# LV.net
KiCad netlist of a schematic drawn in EAGLE
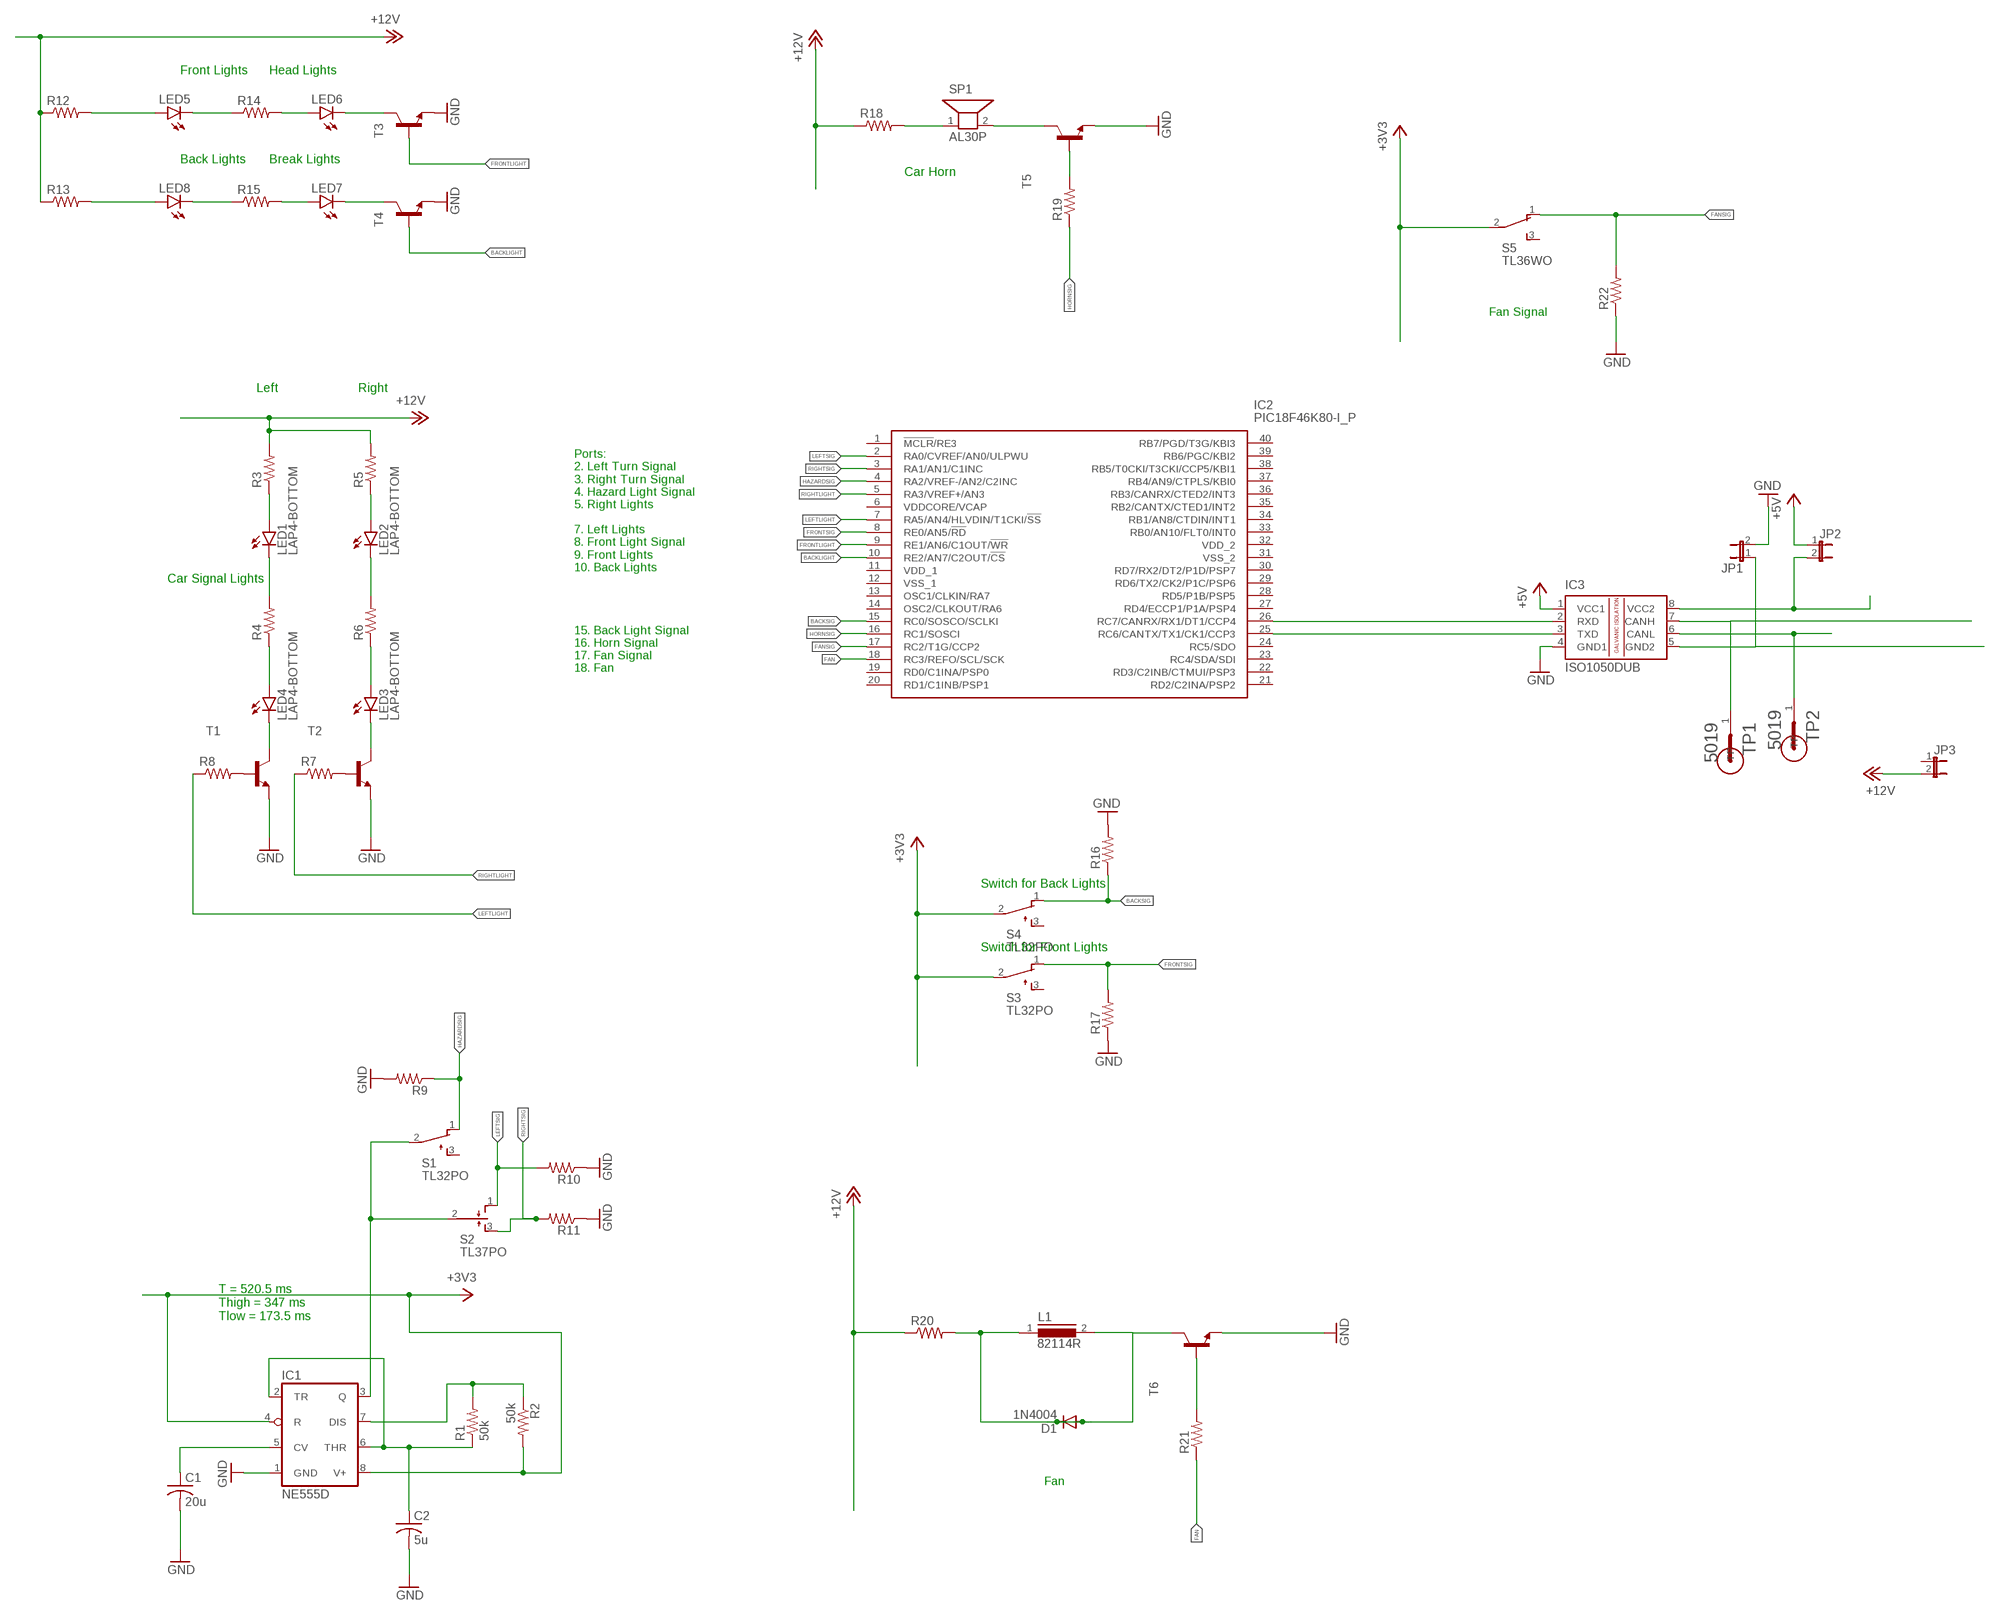
[diagram p0: schematic, sheet 1]

(export (version "E")
  (design (tool "Eeschema 10.0.6"))
  (components
    (comp (ref "C1")
      (value "20u")
      (footprint "eagle-import:C025-024X044")
      (libsource (lib "eagle-import") (part "C-US025-024X044"))
    )
    (comp (ref "C2")
      (value "5u")
      (footprint "eagle-import:C025-024X044")
      (libsource (lib "eagle-import") (part "C-US025-024X044"))
    )
    (comp (ref "D1")
      (value "1N4004")
      (footprint "eagle-import:DO41-10")
      (libsource (lib "eagle-import") (part "1N4004"))
    )
    (comp (ref "IC1")
      (value "NE555D")
      (footprint "eagle-import:SO08")
      (libsource (lib "eagle-import") (part "555DNE"))
    )
    (comp (ref "IC2")
      (value "PIC18F46K80-I_P")
      (footprint "eagle-import:DIP1778W58P254L5175H635Q40N")
      (fields
        (field (name "MANUFACTURER_PART_NUMBER") "PIC18F46K80-I/P")
        (field (name "RS_PART_NUMBER") "7154687P")
      )
      (libsource (lib "eagle-import") (part "PIC18F46K80-I_P"))
    )
    (comp (ref "IC3")
      (value "ISO1050DUB")
      (footprint "eagle-import:DUB-R-PDSO-G8")
      (fields (field (name "MPN") "ISO1050DUBR"))
      (libsource (lib "eagle-import") (part "ISO1050DUB"))
    )
    (comp (ref "JP1")
      (value "JP1E")
      (footprint "eagle-import:JP1")
      (libsource (lib "eagle-import") (part "JP1E"))
    )
    (comp (ref "JP2")
      (value "JP1E")
      (footprint "eagle-import:JP1")
      (libsource (lib "eagle-import") (part "JP1E"))
    )
    (comp (ref "JP3")
      (value "JP1E")
      (footprint "eagle-import:JP1")
      (libsource (lib "eagle-import") (part "JP1E"))
    )
    (comp (ref "L1")
      (value "82114R")
      (footprint "eagle-import:82114R")
      (libsource (lib "eagle-import") (part "82114R"))
    )
    (comp (ref "LED1")
      (value "LAP4-BOTTOM")
      (footprint "eagle-import:P47F-BOTTOM")
      (libsource (lib "eagle-import") (part "P4-BOTTOMLA"))
    )
    (comp (ref "LED2")
      (value "LAP4-BOTTOM")
      (footprint "eagle-import:P47F-BOTTOM")
      (libsource (lib "eagle-import") (part "P4-BOTTOMLA"))
    )
    (comp (ref "LED3")
      (value "LAP4-BOTTOM")
      (footprint "eagle-import:P47F-BOTTOM")
      (libsource (lib "eagle-import") (part "P4-BOTTOMLA"))
    )
    (comp (ref "LED4")
      (value "LAP4-BOTTOM")
      (footprint "eagle-import:P47F-BOTTOM")
      (libsource (lib "eagle-import") (part "P4-BOTTOMLA"))
    )
    (comp (ref "LED5")
      (value "LED")
      (footprint "eagle-import:SMARTLED-TTW")
      (libsource (lib "eagle-import") (part "LED"))
    )
    (comp (ref "LED6")
      (value "LED")
      (footprint "eagle-import:SMARTLED-TTW")
      (libsource (lib "eagle-import") (part "LED"))
    )
    (comp (ref "LED7")
      (value "LED")
      (footprint "eagle-import:SMARTLED-TTW")
      (libsource (lib "eagle-import") (part "LED"))
    )
    (comp (ref "LED8")
      (value "LED")
      (footprint "eagle-import:SMARTLED-TTW")
      (libsource (lib "eagle-import") (part "LED"))
    )
    (comp (ref "R1")
      (value "50k")
      (footprint "eagle-import:0204_7")
      (libsource (lib "eagle-import") (part "R-US_0204/7"))
    )
    (comp (ref "R2")
      (value "50k")
      (footprint "eagle-import:0204_7")
      (libsource (lib "eagle-import") (part "R-US_0204/7"))
    )
    (comp (ref "R3")
      (value "R-US_0204/7")
      (footprint "eagle-import:0204_7")
      (libsource (lib "eagle-import") (part "R-US_0204/7"))
    )
    (comp (ref "R4")
      (value "R-US_0204/7")
      (footprint "eagle-import:0204_7")
      (libsource (lib "eagle-import") (part "R-US_0204/7"))
    )
    (comp (ref "R5")
      (value "R-US_0204/7")
      (footprint "eagle-import:0204_7")
      (libsource (lib "eagle-import") (part "R-US_0204/7"))
    )
    (comp (ref "R6")
      (value "R-US_0204/7")
      (footprint "eagle-import:0204_7")
      (libsource (lib "eagle-import") (part "R-US_0204/7"))
    )
    (comp (ref "R7")
      (value "R-US_0204/7")
      (footprint "eagle-import:0204_7")
      (libsource (lib "eagle-import") (part "R-US_0204/7"))
    )
    (comp (ref "R8")
      (value "R-US_0204/7")
      (footprint "eagle-import:0204_7")
      (libsource (lib "eagle-import") (part "R-US_0204/7"))
    )
    (comp (ref "R9")
      (value "R-US_0204/7")
      (footprint "eagle-import:0204_7")
      (libsource (lib "eagle-import") (part "R-US_0204/7"))
    )
    (comp (ref "R10")
      (value "R-US_0204/7")
      (footprint "eagle-import:0204_7")
      (libsource (lib "eagle-import") (part "R-US_0204/7"))
    )
    (comp (ref "R11")
      (value "R-US_0204/7")
      (footprint "eagle-import:0204_7")
      (libsource (lib "eagle-import") (part "R-US_0204/7"))
    )
    (comp (ref "R12")
      (value "R-US_0204/7")
      (footprint "eagle-import:0204_7")
      (libsource (lib "eagle-import") (part "R-US_0204/7"))
    )
    (comp (ref "R13")
      (value "R-US_0204/7")
      (footprint "eagle-import:0204_7")
      (libsource (lib "eagle-import") (part "R-US_0204/7"))
    )
    (comp (ref "R14")
      (value "R-US_0204/7")
      (footprint "eagle-import:0204_7")
      (libsource (lib "eagle-import") (part "R-US_0204/7"))
    )
    (comp (ref "R15")
      (value "R-US_0204/7")
      (footprint "eagle-import:0204_7")
      (libsource (lib "eagle-import") (part "R-US_0204/7"))
    )
    (comp (ref "R16")
      (value "R-US_0204/7")
      (footprint "eagle-import:0204_7")
      (libsource (lib "eagle-import") (part "R-US_0204/7"))
    )
    (comp (ref "R17")
      (value "R-US_0204/7")
      (footprint "eagle-import:0204_7")
      (libsource (lib "eagle-import") (part "R-US_0204/7"))
    )
    (comp (ref "R18")
      (value "R-US_0204/7")
      (footprint "eagle-import:0204_7")
      (libsource (lib "eagle-import") (part "R-US_0204/7"))
    )
    (comp (ref "R19")
      (value "R-US_0204/7")
      (footprint "eagle-import:0204_7")
      (libsource (lib "eagle-import") (part "R-US_0204/7"))
    )
    (comp (ref "R20")
      (value "R-US_0204/7")
      (footprint "eagle-import:0204_7")
      (libsource (lib "eagle-import") (part "R-US_0204/7"))
    )
    (comp (ref "R21")
      (value "R-US_0204/7")
      (footprint "eagle-import:0204_7")
      (libsource (lib "eagle-import") (part "R-US_0204/7"))
    )
    (comp (ref "R22")
      (value "R-US_0204/7")
      (footprint "eagle-import:0204_7")
      (libsource (lib "eagle-import") (part "R-US_0204/7"))
    )
    (comp (ref "S1")
      (value "TL32PO")
      (footprint "eagle-import:TL3XPO")
      (libsource (lib "eagle-import") (part "TL32PO"))
    )
    (comp (ref "S2")
      (value "TL37PO")
      (footprint "eagle-import:TL3XPO")
      (libsource (lib "eagle-import") (part "TL37PO"))
    )
    (comp (ref "S3")
      (value "TL32PO")
      (footprint "eagle-import:TL3XPO")
      (libsource (lib "eagle-import") (part "TL32PO"))
    )
    (comp (ref "S4")
      (value "TL32PO")
      (footprint "eagle-import:TL3XPO")
      (libsource (lib "eagle-import") (part "TL32PO"))
    )
    (comp (ref "S5")
      (value "TL36WO")
      (footprint "eagle-import:TL3XWO")
      (libsource (lib "eagle-import") (part "TL36WO"))
    )
    (comp (ref "SP1")
      (value "AL30P")
      (footprint "eagle-import:AL30P")
      (libsource (lib "eagle-import") (part "AL30P"))
    )
    (comp (ref "T1")
      (value "-NPN-SOT23-EBC")
      (footprint "eagle-import:SOT23-EBC")
      (libsource (lib "eagle-import") (part "transistor_402_-NPN-SOT23-EBC"))
    )
    (comp (ref "T2")
      (value "-NPN-SOT23-EBC")
      (footprint "eagle-import:SOT23-EBC")
      (libsource (lib "eagle-import") (part "transistor_402_-NPN-SOT23-EBC"))
    )
    (comp (ref "T3")
      (value "-NPN-SOT23-EBC")
      (footprint "eagle-import:SOT23-EBC")
      (libsource (lib "eagle-import") (part "transistor_402_-NPN-SOT23-EBC"))
    )
    (comp (ref "T4")
      (value "-NPN-SOT23-EBC")
      (footprint "eagle-import:SOT23-EBC")
      (libsource (lib "eagle-import") (part "transistor_402_-NPN-SOT23-EBC"))
    )
    (comp (ref "T5")
      (value "-NPN-TO92")
      (footprint "eagle-import:TO92")
      (libsource (lib "eagle-import") (part "-NPN-TO92"))
    )
    (comp (ref "T6")
      (value "-NPN-TO92")
      (footprint "eagle-import:TO92")
      (libsource (lib "eagle-import") (part "-NPN-TO92"))
    )
    (comp (ref "TP1")
      (value "5019")
      (footprint "eagle-import:TP380X203")
      (fields (field (name "MF") "Keystone Electronics"))
      (libsource (lib "eagle-import") (part "5019"))
    )
    (comp (ref "TP2")
      (value "5019")
      (footprint "eagle-import:TP380X203")
      (fields (field (name "MF") "Keystone Electronics"))
      (libsource (lib "eagle-import") (part "5019"))
    )
  )
  (nets
    (net (code "1") (name "+3V3") (class "Default")
      (node (ref "IC1") (pin "4") (pinfunction "R_4") (pintype "input"))
      (node (ref "IC1") (pin "8") (pinfunction "V+_8") (pintype "power_in"))
      (node (ref "R2") (pin "2") (pinfunction "2_2") (pintype "passive"))
      (node (ref "S3") (pin "2") (pinfunction "P_2") (pintype "passive"))
      (node (ref "S4") (pin "2") (pinfunction "P_2") (pintype "passive"))
      (node (ref "S5") (pin "2") (pinfunction "P_2") (pintype "passive"))
    )
    (net (code "2") (name "+5V") (class "Default")
      (node (ref "IC3") (pin "1") (pinfunction "VCC1_1") (pintype "input"))
      (node (ref "JP2") (pin "1") (pinfunction "1_1") (pintype "passive"))
    )
    (net (code "3") (name "+12V") (class "Default")
      (node (ref "JP3") (pin "2") (pinfunction "2_2") (pintype "passive"))
      (node (ref "R12") (pin "1") (pinfunction "1_1") (pintype "passive"))
      (node (ref "R13") (pin "1") (pinfunction "1_1") (pintype "passive"))
      (node (ref "R18") (pin "1") (pinfunction "1_1") (pintype "passive"))
      (node (ref "R20") (pin "1") (pinfunction "1_1") (pintype "passive"))
      (node (ref "R3") (pin "2") (pinfunction "2_2") (pintype "passive"))
      (node (ref "R5") (pin "2") (pinfunction "2_2") (pintype "passive"))
    )
    (net (code "4") (name "BACKLIGHT") (class "Default")
      (node (ref "IC2") (pin "10") (pinfunction "RE2/AN7/C2OUT/~{CS}_10") (pintype "bidirectional"))
      (node (ref "T4") (pin "B") (pinfunction "B_B") (pintype "passive"))
    )
    (net (code "5") (name "BACKSIG") (class "Default")
      (node (ref "IC2") (pin "15") (pinfunction "RC0/SOSCO/SCLKI_15") (pintype "bidirectional"))
      (node (ref "R16") (pin "1") (pinfunction "1_1") (pintype "passive"))
      (node (ref "S4") (pin "1") (pinfunction "O_1") (pintype "passive"))
    )
    (net (code "6") (name "FAN") (class "Default")
      (node (ref "IC2") (pin "18") (pinfunction "RC3/REFO/SCL/SCK_18") (pintype "bidirectional"))
      (node (ref "R21") (pin "1") (pinfunction "1_1") (pintype "passive"))
    )
    (net (code "7") (name "FANSIG") (class "Default")
      (node (ref "IC2") (pin "17") (pinfunction "RC2/T1G/CCP2_17") (pintype "bidirectional"))
      (node (ref "R22") (pin "2") (pinfunction "2_2") (pintype "passive"))
      (node (ref "S5") (pin "1") (pinfunction "O_1") (pintype "passive"))
    )
    (net (code "8") (name "FRONTLIGHT") (class "Default")
      (node (ref "IC2") (pin "9") (pinfunction "RE1/AN6/C1OUT/~{WR}_9") (pintype "bidirectional"))
      (node (ref "T3") (pin "B") (pinfunction "B_B") (pintype "passive"))
    )
    (net (code "9") (name "FRONTSIG") (class "Default")
      (node (ref "IC2") (pin "8") (pinfunction "RE0/AN5/~{RD}_8") (pintype "bidirectional"))
      (node (ref "R17") (pin "2") (pinfunction "2_2") (pintype "passive"))
      (node (ref "S3") (pin "1") (pinfunction "O_1") (pintype "passive"))
    )
    (net (code "10") (name "GND") (class "Default")
      (node (ref "C1") (pin "2") (pinfunction "2_2") (pintype "passive"))
      (node (ref "C2") (pin "2") (pinfunction "2_2") (pintype "passive"))
      (node (ref "IC1") (pin "1") (pinfunction "GND_1") (pintype "power_in"))
      (node (ref "IC3") (pin "4") (pinfunction "GND1_4") (pintype "input"))
      (node (ref "JP1") (pin "2") (pinfunction "2_2") (pintype "passive"))
      (node (ref "R10") (pin "1") (pinfunction "1_1") (pintype "passive"))
      (node (ref "R11") (pin "1") (pinfunction "1_1") (pintype "passive"))
      (node (ref "R16") (pin "2") (pinfunction "2_2") (pintype "passive"))
      (node (ref "R17") (pin "1") (pinfunction "1_1") (pintype "passive"))
      (node (ref "R22") (pin "1") (pinfunction "1_1") (pintype "passive"))
      (node (ref "R9") (pin "2") (pinfunction "2_2") (pintype "passive"))
      (node (ref "T1") (pin "E") (pinfunction "E_E") (pintype "passive"))
      (node (ref "T2") (pin "E") (pinfunction "E_E") (pintype "passive"))
      (node (ref "T3") (pin "E") (pinfunction "E_E") (pintype "passive"))
      (node (ref "T4") (pin "E") (pinfunction "E_E") (pintype "passive"))
      (node (ref "T5") (pin "1") (pinfunction "E_1") (pintype "passive"))
      (node (ref "T6") (pin "1") (pinfunction "E_1") (pintype "passive"))
    )
    (net (code "11") (name "HAZARDSIG") (class "Default")
      (node (ref "IC2") (pin "4") (pinfunction "RA2/VREF-/AN2/C2INC_4") (pintype "bidirectional"))
      (node (ref "R9") (pin "1") (pinfunction "1_1") (pintype "passive"))
      (node (ref "S1") (pin "1") (pinfunction "O_1") (pintype "passive"))
    )
    (net (code "12") (name "HORNSIG") (class "Default")
      (node (ref "IC2") (pin "16") (pinfunction "RC1/SOSCI_16") (pintype "bidirectional"))
      (node (ref "R19") (pin "1") (pinfunction "1_1") (pintype "passive"))
    )
    (net (code "13") (name "LEFTLIGHT") (class "Default")
      (node (ref "IC2") (pin "7") (pinfunction "RA5/AN4/HLVDIN/T1CKI/~{SS}_7") (pintype "bidirectional"))
      (node (ref "R8") (pin "1") (pinfunction "1_1") (pintype "passive"))
    )
    (net (code "14") (name "LEFTSIG") (class "Default")
      (node (ref "IC2") (pin "2") (pinfunction "RA0/CVREF/AN0/ULPWU_2") (pintype "bidirectional"))
      (node (ref "R10") (pin "2") (pinfunction "2_2") (pintype "passive"))
      (node (ref "S2") (pin "1") (pinfunction "O_1") (pintype "passive"))
    )
    (net (code "15") (name "Net-(IC1-CV)") (class "Default")
      (node (ref "C1") (pin "1") (pinfunction "1_1") (pintype "passive"))
      (node (ref "IC1") (pin "5") (pinfunction "CV_5") (pintype "input"))
    )
    (net (code "16") (name "Net-(IC1-DIS)") (class "Default")
      (node (ref "IC1") (pin "7") (pinfunction "DIS_7") (pintype "input"))
      (node (ref "R1") (pin "2") (pinfunction "2_2") (pintype "passive"))
      (node (ref "R2") (pin "1") (pinfunction "1_1") (pintype "passive"))
    )
    (net (code "17") (name "Net-(IC1-Q)") (class "Default")
      (node (ref "IC1") (pin "3") (pinfunction "Q_3") (pintype "output"))
      (node (ref "S1") (pin "2") (pinfunction "P_2") (pintype "passive"))
      (node (ref "S2") (pin "2") (pinfunction "P_2") (pintype "passive"))
    )
    (net (code "18") (name "Net-(IC1-THR)") (class "Default")
      (node (ref "C2") (pin "1") (pinfunction "1_1") (pintype "passive"))
      (node (ref "IC1") (pin "2") (pinfunction "TR_2") (pintype "input"))
      (node (ref "IC1") (pin "6") (pinfunction "THR_6") (pintype "input"))
      (node (ref "R1") (pin "1") (pinfunction "1_1") (pintype "passive"))
    )
    (net (code "19") (name "Net-(IC2-RC6{slash}CANTX{slash}TX1{slash}CK1{slash}CCP3)") (class "Default")
      (node (ref "IC2") (pin "25") (pinfunction "RC6/CANTX/TX1/CK1/CCP3_25") (pintype "bidirectional"))
      (node (ref "IC3") (pin "3") (pinfunction "TXD_3") (pintype "input"))
    )
    (net (code "20") (name "Net-(IC2-RC7{slash}CANRX{slash}RX1{slash}DT1{slash}CCP4)") (class "Default")
      (node (ref "IC2") (pin "26") (pinfunction "RC7/CANRX/RX1/DT1/CCP4_26") (pintype "bidirectional"))
      (node (ref "IC3") (pin "2") (pinfunction "RXD_2") (pintype "input"))
    )
    (net (code "21") (name "Net-(IC3-CANH)") (class "Default")
      (node (ref "IC3") (pin "7") (pinfunction "CANH_7") (pintype "input"))
      (node (ref "TP1") (pin "1") (pinfunction "TP_1") (pintype "passive"))
    )
    (net (code "22") (name "Net-(IC3-CANL)") (class "Default")
      (node (ref "IC3") (pin "6") (pinfunction "CANL_6") (pintype "input"))
      (node (ref "TP2") (pin "1") (pinfunction "TP_1") (pintype "passive"))
    )
    (net (code "23") (name "Net-(IC3-GND2)") (class "Default")
      (node (ref "IC3") (pin "5") (pinfunction "GND2_5") (pintype "input"))
      (node (ref "JP1") (pin "1") (pinfunction "1_1") (pintype "passive"))
    )
    (net (code "24") (name "Net-(IC3-VCC2)") (class "Default")
      (node (ref "IC3") (pin "8") (pinfunction "VCC2_8") (pintype "input"))
      (node (ref "JP2") (pin "2") (pinfunction "2_2") (pintype "passive"))
    )
    (net (code "25") (name "Net-(LED1-PadA)") (class "Default")
      (node (ref "LED1") (pin "A") (pinfunction "A_A") (pintype "passive"))
      (node (ref "R3") (pin "1") (pinfunction "1_1") (pintype "passive"))
    )
    (net (code "26") (name "Net-(LED1-PadC)") (class "Default")
      (node (ref "LED1") (pin "C") (pinfunction "C_C") (pintype "passive"))
      (node (ref "R4") (pin "2") (pinfunction "2_2") (pintype "passive"))
    )
    (net (code "27") (name "Net-(LED2-PadA)") (class "Default")
      (node (ref "LED2") (pin "A") (pinfunction "A_A") (pintype "passive"))
      (node (ref "R5") (pin "1") (pinfunction "1_1") (pintype "passive"))
    )
    (net (code "28") (name "Net-(LED2-PadC)") (class "Default")
      (node (ref "LED2") (pin "C") (pinfunction "C_C") (pintype "passive"))
      (node (ref "R6") (pin "2") (pinfunction "2_2") (pintype "passive"))
    )
    (net (code "29") (name "Net-(LED3-PadA)") (class "Default")
      (node (ref "LED3") (pin "A") (pinfunction "A_A") (pintype "passive"))
      (node (ref "R6") (pin "1") (pinfunction "1_1") (pintype "passive"))
    )
    (net (code "30") (name "Net-(LED3-PadC)") (class "Default")
      (node (ref "LED3") (pin "C") (pinfunction "C_C") (pintype "passive"))
      (node (ref "T2") (pin "C") (pinfunction "C_C") (pintype "passive"))
    )
    (net (code "31") (name "Net-(LED4-PadA)") (class "Default")
      (node (ref "LED4") (pin "A") (pinfunction "A_A") (pintype "passive"))
      (node (ref "R4") (pin "1") (pinfunction "1_1") (pintype "passive"))
    )
    (net (code "32") (name "Net-(LED4-PadC)") (class "Default")
      (node (ref "LED4") (pin "C") (pinfunction "C_C") (pintype "passive"))
      (node (ref "T1") (pin "C") (pinfunction "C_C") (pintype "passive"))
    )
    (net (code "33") (name "Net-(LED5-A)") (class "Default")
      (node (ref "LED5") (pin "A@1") (pinfunction "A_A@1") (pintype "passive"))
      (node (ref "R12") (pin "2") (pinfunction "2_2") (pintype "passive"))
    )
    (net (code "34") (name "Net-(LED5-C)") (class "Default")
      (node (ref "LED5") (pin "C@1") (pinfunction "C_C@1") (pintype "passive"))
      (node (ref "R14") (pin "1") (pinfunction "1_1") (pintype "passive"))
    )
    (net (code "35") (name "Net-(LED6-A)") (class "Default")
      (node (ref "LED6") (pin "A@1") (pinfunction "A_A@1") (pintype "passive"))
      (node (ref "R14") (pin "2") (pinfunction "2_2") (pintype "passive"))
    )
    (net (code "36") (name "Net-(LED6-C)") (class "Default")
      (node (ref "LED6") (pin "C@1") (pinfunction "C_C@1") (pintype "passive"))
      (node (ref "T3") (pin "C") (pinfunction "C_C") (pintype "passive"))
    )
    (net (code "37") (name "Net-(LED7-A)") (class "Default")
      (node (ref "LED7") (pin "A@1") (pinfunction "A_A@1") (pintype "passive"))
      (node (ref "R15") (pin "2") (pinfunction "2_2") (pintype "passive"))
    )
    (net (code "38") (name "Net-(LED7-C)") (class "Default")
      (node (ref "LED7") (pin "C@1") (pinfunction "C_C@1") (pintype "passive"))
      (node (ref "T4") (pin "C") (pinfunction "C_C") (pintype "passive"))
    )
    (net (code "39") (name "Net-(LED8-A)") (class "Default")
      (node (ref "LED8") (pin "A@1") (pinfunction "A_A@1") (pintype "passive"))
      (node (ref "R13") (pin "2") (pinfunction "2_2") (pintype "passive"))
    )
    (net (code "40") (name "Net-(LED8-C)") (class "Default")
      (node (ref "LED8") (pin "C@1") (pinfunction "C_C@1") (pintype "passive"))
      (node (ref "R15") (pin "1") (pinfunction "1_1") (pintype "passive"))
    )
    (net (code "41") (name "Net-(R7-Pad2)") (class "Default")
      (node (ref "R7") (pin "2") (pinfunction "2_2") (pintype "passive"))
      (node (ref "T2") (pin "B") (pinfunction "B_B") (pintype "passive"))
    )
    (net (code "42") (name "Net-(R8-Pad2)") (class "Default")
      (node (ref "R8") (pin "2") (pinfunction "2_2") (pintype "passive"))
      (node (ref "T1") (pin "B") (pinfunction "B_B") (pintype "passive"))
    )
    (net (code "43") (name "Net-(R18-Pad2)") (class "Default")
      (node (ref "R18") (pin "2") (pinfunction "2_2") (pintype "passive"))
      (node (ref "SP1") (pin "1") (pinfunction "1_1") (pintype "passive"))
    )
    (net (code "44") (name "Net-(T5-B)") (class "Default")
      (node (ref "R19") (pin "2") (pinfunction "2_2") (pintype "passive"))
      (node (ref "T5") (pin "2") (pinfunction "B_2") (pintype "passive"))
    )
    (net (code "45") (name "Net-(T5-C)") (class "Default")
      (node (ref "SP1") (pin "2") (pinfunction "2_2") (pintype "passive"))
      (node (ref "T5") (pin "3") (pinfunction "C_3") (pintype "passive"))
    )
    (net (code "46") (name "Net-(T6-B)") (class "Default")
      (node (ref "R21") (pin "2") (pinfunction "2_2") (pintype "passive"))
      (node (ref "T6") (pin "2") (pinfunction "B_2") (pintype "passive"))
    )
    (net (code "47") (name "Net-(T6-C)") (class "Default")
      (node (ref "D1") (pin "A") (pinfunction "A_A") (pintype "passive"))
      (node (ref "D1") (pin "C") (pinfunction "C_C") (pintype "passive"))
      (node (ref "L1") (pin "1") (pinfunction "1_1") (pintype "passive"))
      (node (ref "L1") (pin "2") (pinfunction "2_2") (pintype "passive"))
      (node (ref "R20") (pin "2") (pinfunction "2_2") (pintype "passive"))
      (node (ref "T6") (pin "3") (pinfunction "C_3") (pintype "passive"))
    )
    (net (code "48") (name "RIGHTLIGHT") (class "Default")
      (node (ref "IC2") (pin "5") (pinfunction "RA3/VREF+/AN3_5") (pintype "bidirectional"))
      (node (ref "R7") (pin "1") (pinfunction "1_1") (pintype "passive"))
    )
    (net (code "49") (name "RIGHTSIG") (class "Default")
      (node (ref "IC2") (pin "3") (pinfunction "RA1/AN1/C1INC_3") (pintype "bidirectional"))
      (node (ref "R11") (pin "2") (pinfunction "2_2") (pintype "passive"))
      (node (ref "S2") (pin "3") (pinfunction "S_3") (pintype "passive"))
    )
    (net (code "50") (name "unconnected-(IC2-OSC1{slash}CLKIN{slash}RA7-Pad13)") (class "Default")
      (node (ref "IC2") (pin "13") (pinfunction "OSC1/CLKIN/RA7_13") (pintype "bidirectional"))
    )
    (net (code "51") (name "unconnected-(IC2-OSC2{slash}CLKOUT{slash}RA6-Pad14)") (class "Default")
      (node (ref "IC2") (pin "14") (pinfunction "OSC2/CLKOUT/RA6_14") (pintype "bidirectional"))
    )
    (net (code "52") (name "unconnected-(IC2-RB0{slash}AN10{slash}FLT0{slash}INT0-Pad33)") (class "Default")
      (node (ref "IC2") (pin "33") (pinfunction "RB0/AN10/FLT0/INT0_33") (pintype "bidirectional"))
    )
    (net (code "53") (name "unconnected-(IC2-RB1{slash}AN8{slash}CTDIN{slash}INT1-Pad34)") (class "Default")
      (node (ref "IC2") (pin "34") (pinfunction "RB1/AN8/CTDIN/INT1_34") (pintype "bidirectional"))
    )
    (net (code "54") (name "unconnected-(IC2-RB2{slash}CANTX{slash}CTED1{slash}INT2-Pad35)") (class "Default")
      (node (ref "IC2") (pin "35") (pinfunction "RB2/CANTX/CTED1/INT2_35") (pintype "bidirectional"))
    )
    (net (code "55") (name "unconnected-(IC2-RB3{slash}CANRX{slash}CTED2{slash}INT3-Pad36)") (class "Default")
      (node (ref "IC2") (pin "36") (pinfunction "RB3/CANRX/CTED2/INT3_36") (pintype "bidirectional"))
    )
    (net (code "56") (name "unconnected-(IC2-RB4{slash}AN9{slash}CTPLS{slash}KBI0-Pad37)") (class "Default")
      (node (ref "IC2") (pin "37") (pinfunction "RB4/AN9/CTPLS/KBI0_37") (pintype "bidirectional"))
    )
    (net (code "57") (name "unconnected-(IC2-RB5{slash}T0CKI{slash}T3CKI{slash}CCP5{slash}KBI1-Pad38)") (class "Default")
      (node (ref "IC2") (pin "38") (pinfunction "RB5/T0CKI/T3CKI/CCP5/KBI1_38") (pintype "bidirectional"))
    )
    (net (code "58") (name "unconnected-(IC2-RB6{slash}PGC{slash}KBI2-Pad39)") (class "Default")
      (node (ref "IC2") (pin "39") (pinfunction "RB6/PGC/KBI2_39") (pintype "bidirectional"))
    )
    (net (code "59") (name "unconnected-(IC2-RB7{slash}PGD{slash}T3G{slash}KBI3-Pad40)") (class "Default")
      (node (ref "IC2") (pin "40") (pinfunction "RB7/PGD/T3G/KBI3_40") (pintype "bidirectional"))
    )
    (net (code "60") (name "unconnected-(IC2-RC4{slash}SDA{slash}SDI-Pad23)") (class "Default")
      (node (ref "IC2") (pin "23") (pinfunction "RC4/SDA/SDI_23") (pintype "bidirectional"))
    )
    (net (code "61") (name "unconnected-(IC2-RC5{slash}SDO-Pad24)") (class "Default")
      (node (ref "IC2") (pin "24") (pinfunction "RC5/SDO_24") (pintype "bidirectional"))
    )
    (net (code "62") (name "unconnected-(IC2-RD0{slash}C1INA{slash}PSP0-Pad19)") (class "Default")
      (node (ref "IC2") (pin "19") (pinfunction "RD0/C1INA/PSP0_19") (pintype "bidirectional"))
    )
    (net (code "63") (name "unconnected-(IC2-RD1{slash}C1INB{slash}PSP1-Pad20)") (class "Default")
      (node (ref "IC2") (pin "20") (pinfunction "RD1/C1INB/PSP1_20") (pintype "bidirectional"))
    )
    (net (code "64") (name "unconnected-(IC2-RD2{slash}C2INA{slash}PSP2-Pad21)") (class "Default")
      (node (ref "IC2") (pin "21") (pinfunction "RD2/C2INA/PSP2_21") (pintype "bidirectional"))
    )
    (net (code "65") (name "unconnected-(IC2-RD3{slash}C2INB{slash}CTMUI{slash}PSP3-Pad22)") (class "Default")
      (node (ref "IC2") (pin "22") (pinfunction "RD3/C2INB/CTMUI/PSP3_22") (pintype "bidirectional"))
    )
    (net (code "66") (name "unconnected-(IC2-RD4{slash}ECCP1{slash}P1A{slash}PSP4-Pad27)") (class "Default")
      (node (ref "IC2") (pin "27") (pinfunction "RD4/ECCP1/P1A/PSP4_27") (pintype "bidirectional"))
    )
    (net (code "67") (name "unconnected-(IC2-RD5{slash}P1B{slash}PSP5-Pad28)") (class "Default")
      (node (ref "IC2") (pin "28") (pinfunction "RD5/P1B/PSP5_28") (pintype "bidirectional"))
    )
    (net (code "68") (name "unconnected-(IC2-RD6{slash}TX2{slash}CK2{slash}P1C{slash}PSP6-Pad29)") (class "Default")
      (node (ref "IC2") (pin "29") (pinfunction "RD6/TX2/CK2/P1C/PSP6_29") (pintype "bidirectional"))
    )
    (net (code "69") (name "unconnected-(IC2-RD7{slash}RX2{slash}DT2{slash}P1D{slash}PSP7-Pad30)") (class "Default")
      (node (ref "IC2") (pin "30") (pinfunction "RD7/RX2/DT2/P1D/PSP7_30") (pintype "bidirectional"))
    )
    (net (code "70") (name "unconnected-(IC2-VDDCORE{slash}VCAP-Pad6)") (class "Default")
      (node (ref "IC2") (pin "6") (pinfunction "VDDCORE/VCAP_6") (pintype "bidirectional"))
    )
    (net (code "71") (name "unconnected-(IC2-VDD_1-Pad11)") (class "Default")
      (node (ref "IC2") (pin "11") (pinfunction "VDD_1_11") (pintype "bidirectional"))
    )
    (net (code "72") (name "unconnected-(IC2-VDD_2-Pad32)") (class "Default")
      (node (ref "IC2") (pin "32") (pinfunction "VDD_2_32") (pintype "bidirectional"))
    )
    (net (code "73") (name "unconnected-(IC2-VSS_1-Pad12)") (class "Default")
      (node (ref "IC2") (pin "12") (pinfunction "VSS_1_12") (pintype "bidirectional"))
    )
    (net (code "74") (name "unconnected-(IC2-VSS_2-Pad31)") (class "Default")
      (node (ref "IC2") (pin "31") (pinfunction "VSS_2_31") (pintype "bidirectional"))
    )
    (net (code "75") (name "unconnected-(IC2-~{MCLR}{slash}RE3-Pad1)") (class "Default")
      (node (ref "IC2") (pin "1") (pinfunction "~{MCLR}/RE3_1") (pintype "bidirectional"))
    )
    (net (code "76") (name "unconnected-(JP3-Pad1)") (class "Default")
      (node (ref "JP3") (pin "1") (pinfunction "1_1") (pintype "passive"))
    )
    (net (code "77") (name "unconnected-(S1-S-Pad3)") (class "Default")
      (node (ref "S1") (pin "3") (pinfunction "S_3") (pintype "passive"))
    )
    (net (code "78") (name "unconnected-(S3-S-Pad3)") (class "Default")
      (node (ref "S3") (pin "3") (pinfunction "S_3") (pintype "passive"))
    )
    (net (code "79") (name "unconnected-(S4-S-Pad3)") (class "Default")
      (node (ref "S4") (pin "3") (pinfunction "S_3") (pintype "passive"))
    )
    (net (code "80") (name "unconnected-(S5-S-Pad3)") (class "Default")
      (node (ref "S5") (pin "3") (pinfunction "S_3") (pintype "passive"))
    )
  )
)
